# 4067_to_4051.net
KiCad netlist of a schematic drawn in Altium Designer
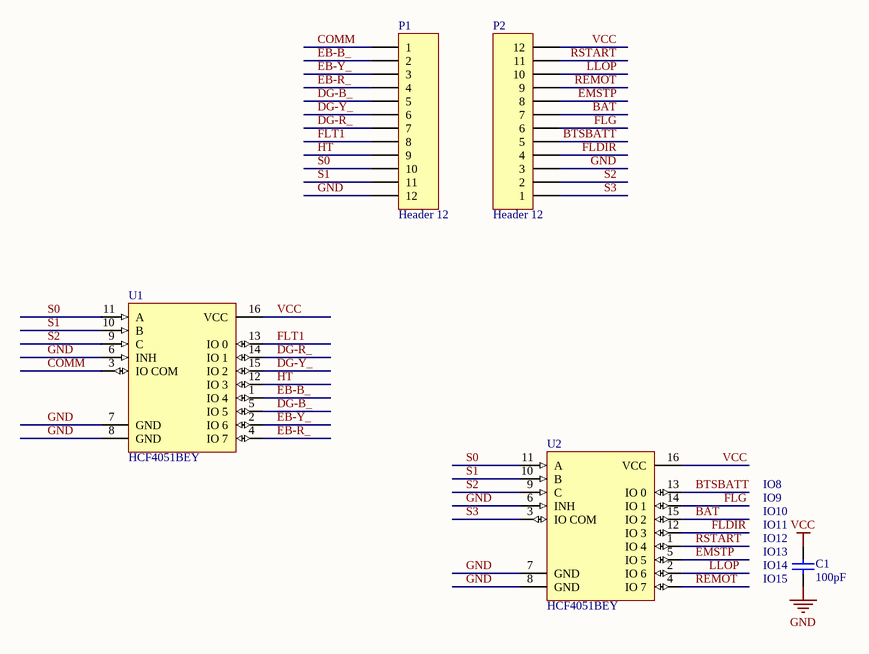
[diagram p0: 4067_to_4051.SchDoc]

(export (version "E")
  (design (tool "Eeschema 10.0.6"))
  (components
    (comp (ref "C1")
      (value "100pF")
      (footprint "C1206_W")
      (description "Capacitor")
      (fields (field (name "Comment") ".1uF 1206") (field (name "PUBLISHER") "Altium Limited"))
      (libsource (lib "Miscellaneous Devices") (part "Cap"))
    )
    (comp (ref "P1")
      (value "Header 12")
      (footprint "HDR1X12")
      (description "Header, 12-Pin")
      (fields (field (name "PUBLISHER") "Altium Limited"))
      (libsource (lib "") (part "Header 12_1"))
    )
    (comp (ref "P2")
      (value "Header 12")
      (footprint "HDR1X12")
      (description "Header, 12-Pin")
      (fields (field (name "PUBLISHER") "Altium Limited"))
      (libsource (lib "Miscellaneous Connectors") (part "Header 12"))
    )
    (comp (ref "U1")
      (value "HCF4051BEY")
      (footprint "DIP16")
      (description "Analog Multiplexer/Demultiplexer")
      (fields (field (name "PUBLISHER") "Altium Limited"))
      (libsource (lib "ST Logic Multiplexer") (part "HCF4051BEY"))
    )
    (comp (ref "U2")
      (value "HCF4051BEY")
      (footprint "DIP16")
      (description "Analog Multiplexer/Demultiplexer")
      (fields (field (name "PUBLISHER") "Altium Limited"))
      (libsource (lib "ST Logic Multiplexer") (part "HCF4051BEY"))
    )
  )
  (nets
    (net (code "1") (name "/BAT") (class "Default")
      (node (ref "P2") (pin "7") (pinfunction "7_7") (pintype "passive"))
      (node (ref "U2") (pin "15") (pinfunction "IO_2_15") (pintype "bidirectional"))
    )
    (net (code "2") (name "/BTSBATT") (class "Default")
      (node (ref "P2") (pin "5") (pinfunction "5_5") (pintype "passive"))
      (node (ref "U2") (pin "13") (pinfunction "IO_0_13") (pintype "bidirectional"))
    )
    (net (code "3") (name "/COMM") (class "Default")
      (node (ref "P1") (pin "1") (pinfunction "1_1") (pintype "passive"))
      (node (ref "U1") (pin "3") (pinfunction "IO_COM_3") (pintype "bidirectional"))
    )
    (net (code "4") (name "/DG-B_") (class "Default")
      (node (ref "P1") (pin "5") (pinfunction "5_5") (pintype "passive"))
      (node (ref "U1") (pin "5") (pinfunction "IO_5_5") (pintype "bidirectional"))
    )
    (net (code "5") (name "/DG-R_") (class "Default")
      (node (ref "P1") (pin "7") (pinfunction "7_7") (pintype "passive"))
      (node (ref "U1") (pin "14") (pinfunction "IO_1_14") (pintype "bidirectional"))
    )
    (net (code "6") (name "/DG-Y_") (class "Default")
      (node (ref "P1") (pin "6") (pinfunction "6_6") (pintype "passive"))
      (node (ref "U1") (pin "15") (pinfunction "IO_2_15") (pintype "bidirectional"))
    )
    (net (code "7") (name "/EB-B_") (class "Default")
      (node (ref "P1") (pin "2") (pinfunction "2_2") (pintype "passive"))
      (node (ref "U1") (pin "1") (pinfunction "IO_4_1") (pintype "bidirectional"))
    )
    (net (code "8") (name "/EB-R_") (class "Default")
      (node (ref "P1") (pin "4") (pinfunction "4_4") (pintype "passive"))
      (node (ref "U1") (pin "4") (pinfunction "IO_7_4") (pintype "bidirectional"))
    )
    (net (code "9") (name "/EB-Y_") (class "Default")
      (node (ref "P1") (pin "3") (pinfunction "3_3") (pintype "passive"))
      (node (ref "U1") (pin "2") (pinfunction "IO_6_2") (pintype "bidirectional"))
    )
    (net (code "10") (name "/EMSTP") (class "Default")
      (node (ref "P2") (pin "8") (pinfunction "8_8") (pintype "passive"))
      (node (ref "U2") (pin "5") (pinfunction "IO_5_5") (pintype "bidirectional"))
    )
    (net (code "11") (name "/FLDIR") (class "Default")
      (node (ref "P2") (pin "4") (pinfunction "4_4") (pintype "passive"))
      (node (ref "U2") (pin "12") (pinfunction "IO_3_12") (pintype "bidirectional"))
    )
    (net (code "12") (name "/FLG") (class "Default")
      (node (ref "P2") (pin "6") (pinfunction "6_6") (pintype "passive"))
      (node (ref "U2") (pin "14") (pinfunction "IO_1_14") (pintype "bidirectional"))
    )
    (net (code "13") (name "/FLT1") (class "Default")
      (node (ref "P1") (pin "8") (pinfunction "8_8") (pintype "passive"))
      (node (ref "U1") (pin "13") (pinfunction "IO_0_13") (pintype "bidirectional"))
    )
    (net (code "14") (name "/HT") (class "Default")
      (node (ref "P1") (pin "9") (pinfunction "9_9") (pintype "passive"))
      (node (ref "U1") (pin "12") (pinfunction "IO_3_12") (pintype "bidirectional"))
    )
    (net (code "15") (name "/LLOP") (class "Default")
      (node (ref "P2") (pin "10") (pinfunction "10_10") (pintype "passive"))
      (node (ref "U2") (pin "2") (pinfunction "IO_6_2") (pintype "bidirectional"))
    )
    (net (code "16") (name "/REMOT") (class "Default")
      (node (ref "P2") (pin "9") (pinfunction "9_9") (pintype "passive"))
      (node (ref "U2") (pin "4") (pinfunction "IO_7_4") (pintype "bidirectional"))
    )
    (net (code "17") (name "/RSTART") (class "Default")
      (node (ref "P2") (pin "11") (pinfunction "11_11") (pintype "passive"))
      (node (ref "U2") (pin "1") (pinfunction "IO_4_1") (pintype "bidirectional"))
    )
    (net (code "18") (name "/S0") (class "Default")
      (node (ref "P1") (pin "10") (pinfunction "10_10") (pintype "passive"))
      (node (ref "U1") (pin "11") (pinfunction "A_11") (pintype "input"))
      (node (ref "U2") (pin "11") (pinfunction "A_11") (pintype "input"))
    )
    (net (code "19") (name "/S1") (class "Default")
      (node (ref "P1") (pin "11") (pinfunction "11_11") (pintype "passive"))
      (node (ref "U1") (pin "10") (pinfunction "B_10") (pintype "input"))
      (node (ref "U2") (pin "10") (pinfunction "B_10") (pintype "input"))
    )
    (net (code "20") (name "/S2") (class "Default")
      (node (ref "P2") (pin "2") (pinfunction "2_2") (pintype "passive"))
      (node (ref "U1") (pin "9") (pinfunction "C_9") (pintype "input"))
      (node (ref "U2") (pin "9") (pinfunction "C_9") (pintype "input"))
    )
    (net (code "21") (name "/S3") (class "Default")
      (node (ref "P2") (pin "1") (pinfunction "1_1") (pintype "passive"))
      (node (ref "U2") (pin "3") (pinfunction "IO_COM_3") (pintype "bidirectional"))
    )
    (net (code "22") (name "GND") (class "Default")
      (node (ref "C1") (pin "1") (pinfunction "1_1") (pintype "passive"))
      (node (ref "P1") (pin "12") (pinfunction "12_12") (pintype "passive"))
      (node (ref "P2") (pin "3") (pinfunction "3_3") (pintype "passive"))
      (node (ref "U1") (pin "6") (pinfunction "INH_6") (pintype "input"))
      (node (ref "U1") (pin "7") (pinfunction "GND_7") (pintype "power_in"))
      (node (ref "U1") (pin "8") (pinfunction "GND_8") (pintype "power_in"))
      (node (ref "U2") (pin "6") (pinfunction "INH_6") (pintype "input"))
      (node (ref "U2") (pin "7") (pinfunction "GND_7") (pintype "power_in"))
      (node (ref "U2") (pin "8") (pinfunction "GND_8") (pintype "power_in"))
    )
    (net (code "23") (name "VCC") (class "Default")
      (node (ref "C1") (pin "2") (pinfunction "2_2") (pintype "passive"))
      (node (ref "P2") (pin "12") (pinfunction "12_12") (pintype "passive"))
      (node (ref "U1") (pin "16") (pinfunction "VCC_16") (pintype "power_in"))
      (node (ref "U2") (pin "16") (pinfunction "VCC_16") (pintype "power_in"))
    )
  )
)
